# battery_monitor_6803-2_-no_uno.net
KiCad netlist of a schematic drawn in EAGLE
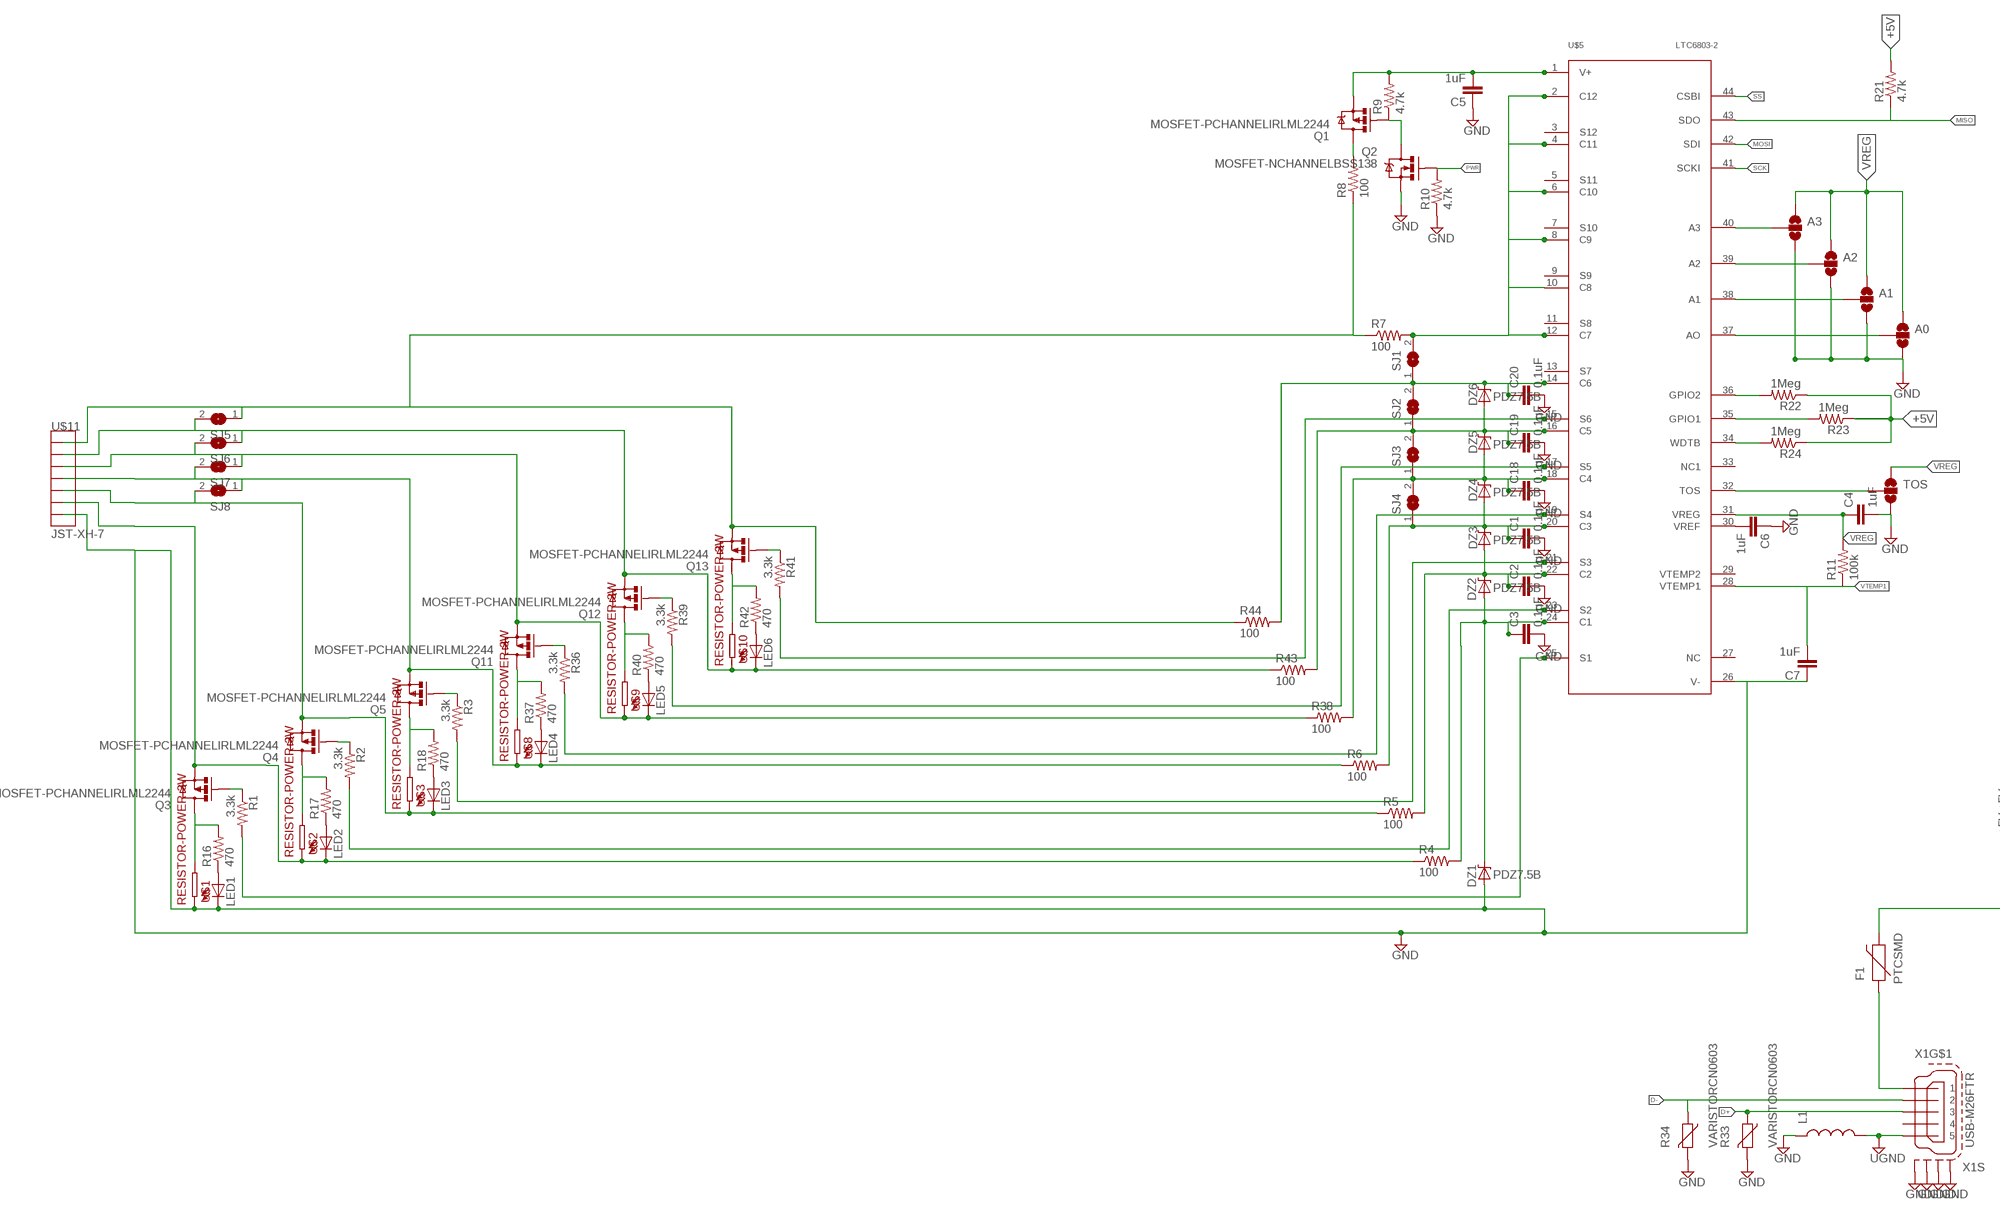
[diagram p0: schematic, sheet 1, part 1 of 2]
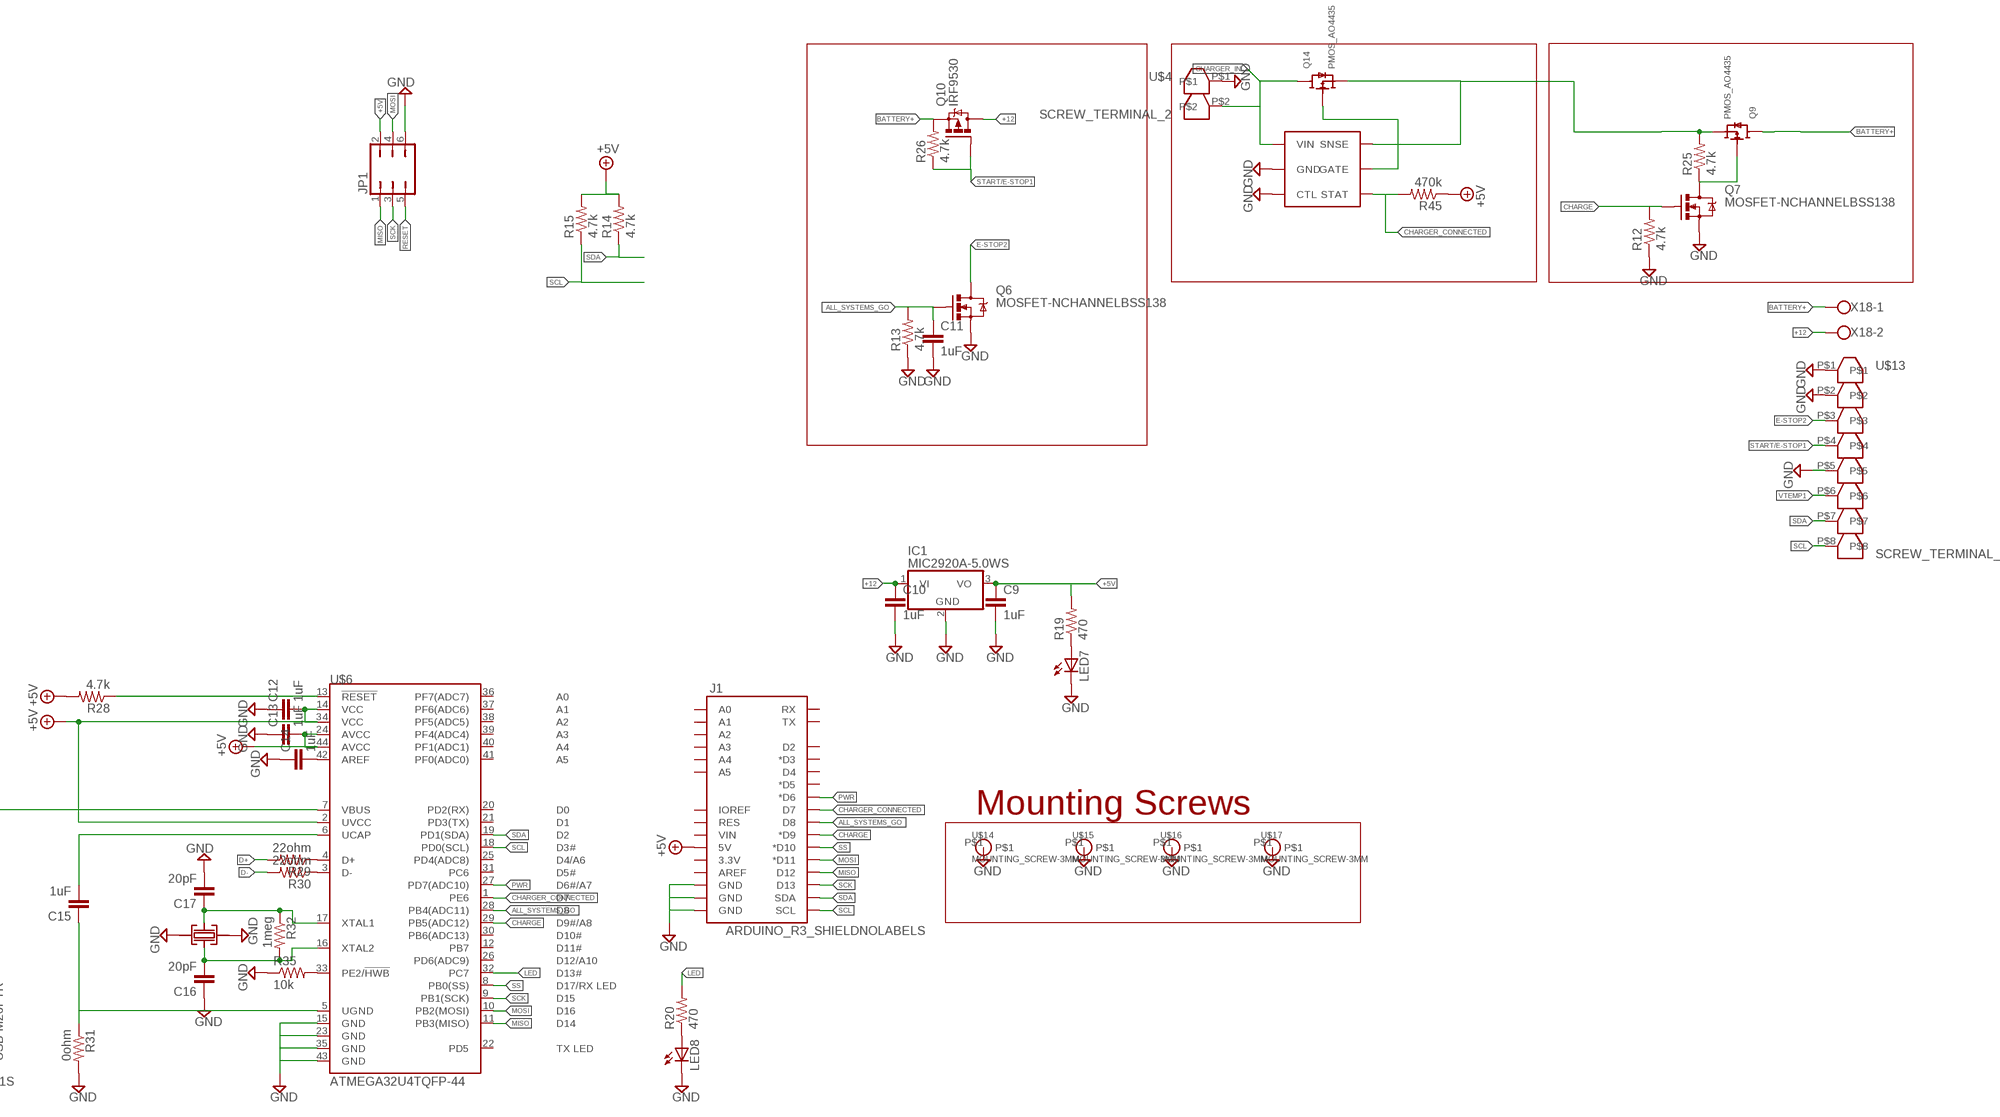
[diagram p1: schematic, sheet 1, part 2 of 2]

(export (version "E")
  (design (tool "Eeschema 10.0.6"))
  (components
    (comp (ref "A0")
      (value "SOLDERJUMPER_2WAYS")
      (footprint "eagle-import:SJ_3")
      (libsource (lib "eagle-import") (part "SOLDERJUMPER_2WAYS"))
    )
    (comp (ref "A1")
      (value "SOLDERJUMPER_2WAYS")
      (footprint "eagle-import:SJ_3")
      (libsource (lib "eagle-import") (part "SOLDERJUMPER_2WAYS"))
    )
    (comp (ref "A2")
      (value "SOLDERJUMPER_2WAYS")
      (footprint "eagle-import:SJ_3")
      (libsource (lib "eagle-import") (part "SOLDERJUMPER_2WAYS"))
    )
    (comp (ref "A3")
      (value "SOLDERJUMPER_2WAYS")
      (footprint "eagle-import:SJ_3")
      (libsource (lib "eagle-import") (part "SOLDERJUMPER_2WAYS"))
    )
    (comp (ref "C1")
      (value "0.1uF")
      (footprint "eagle-import:0603-CAP")
      (fields (field (name "MPN") "0402ZD104KAT2A"))
      (libsource (lib "eagle-import") (part "0.1UF-100V-10%(0603)"))
    )
    (comp (ref "C2")
      (value "0.1uF")
      (footprint "eagle-import:0603-CAP")
      (fields (field (name "MPN") "0402ZD104KAT2A"))
      (libsource (lib "eagle-import") (part "0.1UF-100V-10%(0603)"))
    )
    (comp (ref "C3")
      (value "0.1uF")
      (footprint "eagle-import:0603-CAP")
      (fields (field (name "MPN") "0402ZD104KAT2A"))
      (libsource (lib "eagle-import") (part "0.1UF-100V-10%(0603)"))
    )
    (comp (ref "C4")
      (value "1uF")
      (footprint "eagle-import:0603-CAP")
      (fields (field (name "PROD_ID") "CAP-08390"))
      (libsource (lib "eagle-import") (part "0.1UF-100V-10%(0603)"))
    )
    (comp (ref "C5")
      (value "1uF")
      (footprint "eagle-import:0603-CAP")
      (fields (field (name "PROD_ID") "CAP-08390"))
      (libsource (lib "eagle-import") (part "0.1UF-100V-10%(0603)"))
    )
    (comp (ref "C6")
      (value "1uF")
      (footprint "eagle-import:0603-CAP")
      (fields (field (name "PROD_ID") "CAP-08390"))
      (libsource (lib "eagle-import") (part "0.1UF-100V-10%(0603)"))
    )
    (comp (ref "C7")
      (value "1uF")
      (footprint "eagle-import:0603-CAP")
      (fields (field (name "PROD_ID") "CAP-08390"))
      (libsource (lib "eagle-import") (part "0.1UF-100V-10%(0603)"))
    )
    (comp (ref "C9")
      (value "1uF")
      (footprint "eagle-import:0603-CAP")
      (fields (field (name "PROD_ID") "CAP-08390"))
      (libsource (lib "eagle-import") (part "0.1UF-100V-10%(0603)"))
    )
    (comp (ref "C10")
      (value "1uF")
      (footprint "eagle-import:0603-CAP")
      (fields (field (name "PROD_ID") "CAP-08390"))
      (libsource (lib "eagle-import") (part "0.1UF-100V-10%(0603)"))
    )
    (comp (ref "C11")
      (value "1uF")
      (footprint "eagle-import:0603-CAP")
      (fields (field (name "PROD_ID") "CAP-08390"))
      (libsource (lib "eagle-import") (part "0.1UF-100V-10%(0603)"))
    )
    (comp (ref "C12")
      (value "1uF")
      (footprint "eagle-import:0603-CAP")
      (fields (field (name "PROD_ID") "CAP-08390"))
      (libsource (lib "eagle-import") (part "0.1UF-100V-10%(0603)"))
    )
    (comp (ref "C13")
      (value "1uF")
      (footprint "eagle-import:0603-CAP")
      (fields (field (name "PROD_ID") "CAP-08390"))
      (libsource (lib "eagle-import") (part "0.1UF-100V-10%(0603)"))
    )
    (comp (ref "C14")
      (value "1uF")
      (footprint "eagle-import:0603-CAP")
      (fields (field (name "PROD_ID") "CAP-08390"))
      (libsource (lib "eagle-import") (part "0.1UF-100V-10%(0603)"))
    )
    (comp (ref "C15")
      (value "1uF")
      (footprint "eagle-import:0603-CAP")
      (fields (field (name "PROD_ID") "CAP-08390"))
      (libsource (lib "eagle-import") (part "0.1UF-100V-10%(0603)"))
    )
    (comp (ref "C16")
      (value "20pF")
      (footprint "eagle-import:0603-CAP")
      (fields (field (name "PROD_ID") "CAP-08390"))
      (libsource (lib "eagle-import") (part "0.1UF-100V-10%(0603)"))
    )
    (comp (ref "C17")
      (value "20pF")
      (footprint "eagle-import:0603-CAP")
      (fields (field (name "PROD_ID") "CAP-08390"))
      (libsource (lib "eagle-import") (part "0.1UF-100V-10%(0603)"))
    )
    (comp (ref "C18")
      (value "0.1uF")
      (footprint "eagle-import:0603-CAP")
      (fields (field (name "MPN") "0402ZD104KAT2A") (field (name "PROD_ID") "CAP-08390"))
      (libsource (lib "eagle-import") (part "0.1UF-100V-10%(0603)"))
    )
    (comp (ref "C19")
      (value "0.1uF")
      (footprint "eagle-import:0603-CAP")
      (fields (field (name "MPN") "0402ZD104KAT2A") (field (name "PROD_ID") "CAP-08390"))
      (libsource (lib "eagle-import") (part "0.1UF-100V-10%(0603)"))
    )
    (comp (ref "C20")
      (value "0.1uF")
      (footprint "eagle-import:0603-CAP")
      (fields (field (name "MPN") "0402ZD104KAT2A") (field (name "PROD_ID") "CAP-08390"))
      (libsource (lib "eagle-import") (part "0.1UF-100V-10%(0603)"))
    )
    (comp (ref "DZ1")
      (value "PDZ7.5B")
      (footprint "eagle-import:SOD-323")
      (libsource (lib "eagle-import") (part "DIODE-ZENER-BZT52"))
    )
    (comp (ref "DZ2")
      (value "PDZ7.5B")
      (footprint "eagle-import:SOD-323")
      (libsource (lib "eagle-import") (part "DIODE-ZENER-BZT52"))
    )
    (comp (ref "DZ3")
      (value "PDZ7.5B")
      (footprint "eagle-import:SOD-323")
      (libsource (lib "eagle-import") (part "DIODE-ZENER-BZT52"))
    )
    (comp (ref "DZ4")
      (value "PDZ7.5B")
      (footprint "eagle-import:SOD-323")
      (libsource (lib "eagle-import") (part "DIODE-ZENER-BZT52"))
    )
    (comp (ref "DZ5")
      (value "PDZ7.5B")
      (footprint "eagle-import:SOD-323")
      (libsource (lib "eagle-import") (part "DIODE-ZENER-BZT52"))
    )
    (comp (ref "DZ6")
      (value "PDZ7.5B")
      (footprint "eagle-import:SOD-323")
      (libsource (lib "eagle-import") (part "DIODE-ZENER-BZT52"))
    )
    (comp (ref "F1")
      (value "PTCSMD")
      (footprint "eagle-import:PTC-1206")
      (libsource (lib "eagle-import") (part "PTCSMD"))
    )
    (comp (ref "IC1")
      (value "MIC2920A-5.0WS")
      (footprint "eagle-import:SOT223")
      (libsource (lib "eagle-import") (part "MCP1703DB"))
    )
    (comp (ref "J1")
      (value "ARDUINO_R3_SHIELDNOLABELS")
      (footprint "eagle-import:UNO_R3_SHIELD_NOLABELS")
      (libsource (lib "eagle-import") (part "ARDUINO_R3_SHIELDNOLABELS"))
    )
    (comp (ref "JP1")
      (value "JP3Q")
      (footprint "eagle-import:JP3Q")
      (libsource (lib "eagle-import") (part "JP3Q"))
    )
    (comp (ref "L1")
      (value "INDUCTOR0805")
      (footprint "eagle-import:0805")
      (libsource (lib "eagle-import") (part "INDUCTOR0805"))
    )
    (comp (ref "LED1")
      (value "LED0603")
      (footprint "eagle-import:LED-0603")
      (libsource (lib "eagle-import") (part "LED0603"))
    )
    (comp (ref "LED2")
      (value "LED0603")
      (footprint "eagle-import:LED-0603")
      (libsource (lib "eagle-import") (part "LED0603"))
    )
    (comp (ref "LED3")
      (value "LED0603")
      (footprint "eagle-import:LED-0603")
      (libsource (lib "eagle-import") (part "LED0603"))
    )
    (comp (ref "LED4")
      (value "LED0603")
      (footprint "eagle-import:LED-0603")
      (libsource (lib "eagle-import") (part "LED0603"))
    )
    (comp (ref "LED5")
      (value "LED0603")
      (footprint "eagle-import:LED-0603")
      (libsource (lib "eagle-import") (part "LED0603"))
    )
    (comp (ref "LED6")
      (value "LED0603")
      (footprint "eagle-import:LED-0603")
      (libsource (lib "eagle-import") (part "LED0603"))
    )
    (comp (ref "LED7")
      (value "LED0603")
      (footprint "eagle-import:LED-0603")
      (libsource (lib "eagle-import") (part "LED0603"))
    )
    (comp (ref "LED8")
      (value "LED0603")
      (footprint "eagle-import:LED-0603")
      (libsource (lib "eagle-import") (part "LED0603"))
    )
    (comp (ref "Q1")
      (value "MOSFET-PCHANNELIRLML2244")
      (footprint "eagle-import:SOT23-3")
      (libsource (lib "eagle-import") (part "MOSFET-PCHANNELIRLML2244"))
    )
    (comp (ref "Q2")
      (value "MOSFET-NCHANNELBSS138")
      (footprint "eagle-import:SOT23")
      (libsource (lib "eagle-import") (part "MOSFET-NCHANNELBSS138"))
    )
    (comp (ref "Q3")
      (value "MOSFET-PCHANNELIRLML2244")
      (footprint "eagle-import:SOT23-3")
      (libsource (lib "eagle-import") (part "MOSFET-PCHANNELIRLML2244"))
    )
    (comp (ref "Q4")
      (value "MOSFET-PCHANNELIRLML2244")
      (footprint "eagle-import:SOT23-3")
      (libsource (lib "eagle-import") (part "MOSFET-PCHANNELIRLML2244"))
    )
    (comp (ref "Q5")
      (value "MOSFET-PCHANNELIRLML2244")
      (footprint "eagle-import:SOT23-3")
      (libsource (lib "eagle-import") (part "MOSFET-PCHANNELIRLML2244"))
    )
    (comp (ref "Q6")
      (value "MOSFET-NCHANNELBSS138")
      (footprint "eagle-import:SOT23")
      (libsource (lib "eagle-import") (part "MOSFET-NCHANNELBSS138"))
    )
    (comp (ref "Q7")
      (value "MOSFET-NCHANNELBSS138")
      (footprint "eagle-import:SOT23")
      (libsource (lib "eagle-import") (part "MOSFET-NCHANNELBSS138"))
    )
    (comp (ref "Q9")
      (value "PMOS_AO4435")
      (footprint "eagle-import:SOIC8")
      (libsource (lib "eagle-import") (part "PMOS_AO4435"))
    )
    (comp (ref "Q10")
      (value "IRF9530")
      (footprint "eagle-import:TO220BV")
      (libsource (lib "eagle-import") (part "IRF9530"))
    )
    (comp (ref "Q11")
      (value "MOSFET-PCHANNELIRLML2244")
      (footprint "eagle-import:SOT23-3")
      (libsource (lib "eagle-import") (part "MOSFET-PCHANNELIRLML2244"))
    )
    (comp (ref "Q12")
      (value "MOSFET-PCHANNELIRLML2244")
      (footprint "eagle-import:SOT23-3")
      (libsource (lib "eagle-import") (part "MOSFET-PCHANNELIRLML2244"))
    )
    (comp (ref "Q13")
      (value "MOSFET-PCHANNELIRLML2244")
      (footprint "eagle-import:SOT23-3")
      (libsource (lib "eagle-import") (part "MOSFET-PCHANNELIRLML2244"))
    )
    (comp (ref "Q14")
      (value "PMOS_AO4435")
      (footprint "eagle-import:SOIC8")
      (libsource (lib "eagle-import") (part "PMOS_AO4435"))
    )
    (comp (ref "R1")
      (value "3.3k")
      (footprint "eagle-import:0603-RES")
      (libsource (lib "eagle-import") (part "3.3KOHM1/10W1%(0603)"))
    )
    (comp (ref "R2")
      (value "3.3k")
      (footprint "eagle-import:0603-RES")
      (libsource (lib "eagle-import") (part "3.3KOHM1/10W1%(0603)"))
    )
    (comp (ref "R3")
      (value "3.3k")
      (footprint "eagle-import:0603-RES")
      (libsource (lib "eagle-import") (part "3.3KOHM1/10W1%(0603)"))
    )
    (comp (ref "R4")
      (value "100")
      (footprint "eagle-import:0603-RES")
      (libsource (lib "eagle-import") (part "3.3KOHM1/10W1%(0603)"))
    )
    (comp (ref "R5")
      (value "100")
      (footprint "eagle-import:0603-RES")
      (libsource (lib "eagle-import") (part "3.3KOHM1/10W1%(0603)"))
    )
    (comp (ref "R6")
      (value "100")
      (footprint "eagle-import:0603-RES")
      (libsource (lib "eagle-import") (part "3.3KOHM1/10W1%(0603)"))
    )
    (comp (ref "R7")
      (value "100")
      (footprint "eagle-import:0603-RES")
      (libsource (lib "eagle-import") (part "3.3KOHM1/10W1%(0603)"))
    )
    (comp (ref "R8")
      (value "100")
      (footprint "eagle-import:0603-RES")
      (libsource (lib "eagle-import") (part "3.3KOHM1/10W1%(0603)"))
    )
    (comp (ref "R9")
      (value "4.7k")
      (footprint "eagle-import:0603-RES")
      (libsource (lib "eagle-import") (part "3.3KOHM1/10W1%(0603)"))
    )
    (comp (ref "R10")
      (value "4.7k")
      (footprint "eagle-import:0603-RES")
      (libsource (lib "eagle-import") (part "3.3KOHM1/10W1%(0603)"))
    )
    (comp (ref "R11")
      (value "100k")
      (footprint "eagle-import:0603-RES")
      (libsource (lib "eagle-import") (part "3.3KOHM1/10W1%(0603)"))
    )
    (comp (ref "R12")
      (value "4.7k")
      (footprint "eagle-import:0603-RES")
      (libsource (lib "eagle-import") (part "3.3KOHM1/10W1%(0603)"))
    )
    (comp (ref "R13")
      (value "4.7k")
      (footprint "eagle-import:0603-RES")
      (libsource (lib "eagle-import") (part "3.3KOHM1/10W1%(0603)"))
    )
    (comp (ref "R14")
      (value "4.7k")
      (footprint "eagle-import:0603-RES")
      (libsource (lib "eagle-import") (part "3.3KOHM1/10W1%(0603)"))
    )
    (comp (ref "R15")
      (value "4.7k")
      (footprint "eagle-import:0603-RES")
      (libsource (lib "eagle-import") (part "3.3KOHM1/10W1%(0603)"))
    )
    (comp (ref "R16")
      (value "470")
      (footprint "eagle-import:0603-RES")
      (fields (field (name "PROD_ID") "RES-07851"))
      (libsource (lib "eagle-import") (part "3.3KOHM1/10W1%(0603)"))
    )
    (comp (ref "R17")
      (value "470")
      (footprint "eagle-import:0603-RES")
      (fields (field (name "PROD_ID") "RES-07851"))
      (libsource (lib "eagle-import") (part "3.3KOHM1/10W1%(0603)"))
    )
    (comp (ref "R18")
      (value "470")
      (footprint "eagle-import:0603-RES")
      (fields (field (name "PROD_ID") "RES-07851"))
      (libsource (lib "eagle-import") (part "3.3KOHM1/10W1%(0603)"))
    )
    (comp (ref "R19")
      (value "470")
      (footprint "eagle-import:0603-RES")
      (fields (field (name "PROD_ID") "RES-07851"))
      (libsource (lib "eagle-import") (part "3.3KOHM1/10W1%(0603)"))
    )
    (comp (ref "R20")
      (value "470")
      (footprint "eagle-import:0603-RES")
      (fields (field (name "PROD_ID") "RES-07851"))
      (libsource (lib "eagle-import") (part "3.3KOHM1/10W1%(0603)"))
    )
    (comp (ref "R21")
      (value "4.7k")
      (footprint "eagle-import:0603-RES")
      (fields (field (name "PROD_ID") "RES-07851"))
      (libsource (lib "eagle-import") (part "3.3KOHM1/10W1%(0603)"))
    )
    (comp (ref "R22")
      (value "1Meg")
      (footprint "eagle-import:0603-RES")
      (fields (field (name "PROD_ID") "RES-07851"))
      (libsource (lib "eagle-import") (part "3.3KOHM1/10W1%(0603)"))
    )
    (comp (ref "R23")
      (value "1Meg")
      (footprint "eagle-import:0603-RES")
      (fields (field (name "PROD_ID") "RES-07851"))
      (libsource (lib "eagle-import") (part "3.3KOHM1/10W1%(0603)"))
    )
    (comp (ref "R24")
      (value "1Meg")
      (footprint "eagle-import:0603-RES")
      (fields (field (name "PROD_ID") "RES-07851"))
      (libsource (lib "eagle-import") (part "3.3KOHM1/10W1%(0603)"))
    )
    (comp (ref "R25")
      (value "4.7k")
      (footprint "eagle-import:0603-RES")
      (fields (field (name "PROD_ID") "RES-07851"))
      (libsource (lib "eagle-import") (part "3.3KOHM1/10W1%(0603)"))
    )
    (comp (ref "R26")
      (value "4.7k")
      (footprint "eagle-import:0603-RES")
      (fields (field (name "PROD_ID") "RES-07851"))
      (libsource (lib "eagle-import") (part "3.3KOHM1/10W1%(0603)"))
    )
    (comp (ref "R28")
      (value "4.7k")
      (footprint "eagle-import:0603-RES")
      (fields (field (name "PROD_ID") "RES-07851"))
      (libsource (lib "eagle-import") (part "3.3KOHM1/10W1%(0603)"))
    )
    (comp (ref "R29")
      (value "22ohm")
      (footprint "eagle-import:0603-RES")
      (fields (field (name "PROD_ID") "RES-07851"))
      (libsource (lib "eagle-import") (part "3.3KOHM1/10W1%(0603)"))
    )
    (comp (ref "R30")
      (value "22ohm")
      (footprint "eagle-import:0603-RES")
      (fields (field (name "PROD_ID") "RES-07851"))
      (libsource (lib "eagle-import") (part "3.3KOHM1/10W1%(0603)"))
    )
    (comp (ref "R31")
      (value "0ohm")
      (footprint "eagle-import:0603-RES")
      (fields (field (name "PROD_ID") "RES-07851"))
      (libsource (lib "eagle-import") (part "3.3KOHM1/10W1%(0603)"))
    )
    (comp (ref "R32")
      (value "1meg")
      (footprint "eagle-import:0603-RES")
      (fields (field (name "PROD_ID") "RES-07851"))
      (libsource (lib "eagle-import") (part "3.3KOHM1/10W1%(0603)"))
    )
    (comp (ref "R33")
      (value "VARISTORCN0603")
      (footprint "eagle-import:CT_CN0603")
      (libsource (lib "eagle-import") (part "VARISTORCN0603"))
    )
    (comp (ref "R34")
      (value "VARISTORCN0603")
      (footprint "eagle-import:CT_CN0603")
      (libsource (lib "eagle-import") (part "VARISTORCN0603"))
    )
    (comp (ref "R35")
      (value "10k")
      (footprint "eagle-import:0603-RES")
      (fields (field (name "PROD_ID") "RES-07851"))
      (libsource (lib "eagle-import") (part "3.3KOHM1/10W1%(0603)"))
    )
    (comp (ref "R36")
      (value "3.3k")
      (footprint "eagle-import:0603-RES")
      (libsource (lib "eagle-import") (part "3.3KOHM1/10W1%(0603)"))
    )
    (comp (ref "R37")
      (value "470")
      (footprint "eagle-import:0603-RES")
      (fields (field (name "PROD_ID") "RES-07851"))
      (libsource (lib "eagle-import") (part "3.3KOHM1/10W1%(0603)"))
    )
    (comp (ref "R38")
      (value "100")
      (footprint "eagle-import:0603-RES")
      (fields (field (name "PROD_ID") "RES-07851"))
      (libsource (lib "eagle-import") (part "3.3KOHM1/10W1%(0603)"))
    )
    (comp (ref "R39")
      (value "3.3k")
      (footprint "eagle-import:0603-RES")
      (libsource (lib "eagle-import") (part "3.3KOHM1/10W1%(0603)"))
    )
    (comp (ref "R40")
      (value "470")
      (footprint "eagle-import:0603-RES")
      (fields (field (name "PROD_ID") "RES-07851"))
      (libsource (lib "eagle-import") (part "3.3KOHM1/10W1%(0603)"))
    )
    (comp (ref "R41")
      (value "3.3k")
      (footprint "eagle-import:0603-RES")
      (libsource (lib "eagle-import") (part "3.3KOHM1/10W1%(0603)"))
    )
    (comp (ref "R42")
      (value "470")
      (footprint "eagle-import:0603-RES")
      (fields (field (name "PROD_ID") "RES-07851"))
      (libsource (lib "eagle-import") (part "3.3KOHM1/10W1%(0603)"))
    )
    (comp (ref "R43")
      (value "100")
      (footprint "eagle-import:0603-RES")
      (fields (field (name "PROD_ID") "RES-07851"))
      (libsource (lib "eagle-import") (part "3.3KOHM1/10W1%(0603)"))
    )
    (comp (ref "R44")
      (value "100")
      (footprint "eagle-import:0603-RES")
      (fields (field (name "PROD_ID") "RES-07851"))
      (libsource (lib "eagle-import") (part "3.3KOHM1/10W1%(0603)"))
    )
    (comp (ref "R45")
      (value "470k")
      (footprint "eagle-import:0603-RES")
      (fields (field (name "PROD_ID") "RES-07851"))
      (libsource (lib "eagle-import") (part "3.3KOHM1/10W1%(0603)"))
    )
    (comp (ref "SJ1") (value "SJ") (footprint "eagle-import:SJ") (libsource (lib "eagle-import") (part "SJ")))
    (comp (ref "SJ2") (value "SJ") (footprint "eagle-import:SJ") (libsource (lib "eagle-import") (part "SJ")))
    (comp (ref "SJ3") (value "SJ") (footprint "eagle-import:SJ") (libsource (lib "eagle-import") (part "SJ")))
    (comp (ref "SJ4") (value "SJ") (footprint "eagle-import:SJ") (libsource (lib "eagle-import") (part "SJ")))
    (comp (ref "SJ5") (value "SJ") (footprint "eagle-import:SJ") (libsource (lib "eagle-import") (part "SJ")))
    (comp (ref "SJ6") (value "SJ") (footprint "eagle-import:SJ") (libsource (lib "eagle-import") (part "SJ")))
    (comp (ref "SJ7") (value "SJ") (footprint "eagle-import:SJ") (libsource (lib "eagle-import") (part "SJ")))
    (comp (ref "SJ8") (value "SJ") (footprint "eagle-import:SJ") (libsource (lib "eagle-import") (part "SJ")))
    (comp (ref "TOS")
      (value "SOLDERJUMPER_2WAYS")
      (footprint "eagle-import:SJ_3")
      (libsource (lib "eagle-import") (part "SOLDERJUMPER_2WAYS"))
    )
    (comp (ref "U$1")
      (value "RESISTOR-POWER-3W")
      (footprint "eagle-import:RESISTOR-3W")
      (libsource (lib "eagle-import") (part "RESISTOR-POWER-3W"))
    )
    (comp (ref "U$2")
      (value "RESISTOR-POWER-3W")
      (footprint "eagle-import:RESISTOR-3W")
      (libsource (lib "eagle-import") (part "RESISTOR-POWER-3W"))
    )
    (comp (ref "U$3")
      (value "RESISTOR-POWER-3W")
      (footprint "eagle-import:RESISTOR-3W")
      (libsource (lib "eagle-import") (part "RESISTOR-POWER-3W"))
    )
    (comp (ref "U$4")
      (value "SCREW_TERMINAL_2")
      (footprint "eagle-import:SCREW_TERMINAL_2")
      (libsource (lib "eagle-import") (part "SCREW_TERMINAL_2"))
    )
    (comp (ref "U$5")
      (value "LTC6803-2")
      (footprint "eagle-import:FSOP-44")
      (libsource (lib "eagle-import") (part "LTC6803-2"))
    )
    (comp (ref "U$6")
      (value "ATMEGA32U4TQFP-44")
      (footprint "eagle-import:TQFP44")
      (libsource (lib "eagle-import") (part "ATMEGA32U4TQFP-44"))
    )
    (comp (ref "U$7")
      (value "CRYSTAL_403")
      (footprint "eagle-import:CRYSTAL(DFN,LCC)")
      (libsource (lib "eagle-import") (part "CRYSTAL_403"))
    )
    (comp (ref "U$8")
      (value "RESISTOR-POWER-3W")
      (footprint "eagle-import:RESISTOR-3W")
      (libsource (lib "eagle-import") (part "RESISTOR-POWER-3W"))
    )
    (comp (ref "U$9")
      (value "RESISTOR-POWER-3W")
      (footprint "eagle-import:RESISTOR-3W")
      (libsource (lib "eagle-import") (part "RESISTOR-POWER-3W"))
    )
    (comp (ref "U$10")
      (value "RESISTOR-POWER-3W")
      (footprint "eagle-import:RESISTOR-3W")
      (libsource (lib "eagle-import") (part "RESISTOR-POWER-3W"))
    )
    (comp (ref "U$11")
      (value "JST-XH-7")
      (footprint "eagle-import:JST-XH-7")
      (libsource (lib "eagle-import") (part "JST-XH-7"))
    )
    (comp (ref "U$12")
      (value "LTC4412")
      (footprint "eagle-import:SOT-23-6")
      (libsource (lib "eagle-import") (part "LTC4412"))
    )
    (comp (ref "U$13")
      (value "SCREW_TERMINAL_8")
      (footprint "eagle-import:SCREW_TERMINAL_8")
      (libsource (lib "eagle-import") (part "SCREW_TERMINAL_8"))
    )
    (comp (ref "U$14")
      (value "MOUNTING_SCREW-3MM")
      (footprint "eagle-import:MOUNTING_SCREW-3MM")
      (libsource (lib "eagle-import") (part "MOUNTING_SCREW-3MM"))
    )
    (comp (ref "U$15")
      (value "MOUNTING_SCREW-3MM")
      (footprint "eagle-import:MOUNTING_SCREW-3MM")
      (libsource (lib "eagle-import") (part "MOUNTING_SCREW-3MM"))
    )
    (comp (ref "U$16")
      (value "MOUNTING_SCREW-3MM")
      (footprint "eagle-import:MOUNTING_SCREW-3MM")
      (libsource (lib "eagle-import") (part "MOUNTING_SCREW-3MM"))
    )
    (comp (ref "U$17")
      (value "MOUNTING_SCREW-3MM")
      (footprint "eagle-import:MOUNTING_SCREW-3MM")
      (libsource (lib "eagle-import") (part "MOUNTING_SCREW-3MM"))
    )
    (comp (ref "X1")
      (value "USB-M26FTR")
      (footprint "eagle-import:32005-301")
      (libsource (lib "eagle-import") (part "MINI-USB-SCHIELD-32005-301"))
    )
    (comp (ref "X18")
      (value "W237-102")
      (footprint "eagle-import:W237-102")
      (fields (field (name "MPN") "237-102") (field (name "OC_NEWARK") "unknown"))
      (libsource (lib "eagle-import") (part "W237-102"))
    )
  )
  (nets
    (net (code "1") (name "+5V") (class "Default")
      (node (ref "C12") (pin "2") (pinfunction "2_2") (pintype "passive"))
      (node (ref "C13") (pin "2") (pinfunction "2_2") (pintype "passive"))
      (node (ref "C9") (pin "1") (pinfunction "1_1") (pintype "passive"))
      (node (ref "IC1") (pin "3") (pinfunction "VO_3") (pintype "passive"))
      (node (ref "J1") (pin "5V") (pinfunction "5V_5V") (pintype "bidirectional"))
      (node (ref "JP1") (pin "2") (pinfunction "2_2") (pintype "passive"))
      (node (ref "R14") (pin "2") (pinfunction "2_2") (pintype "passive"))
      (node (ref "R15") (pin "2") (pinfunction "2_2") (pintype "passive"))
      (node (ref "R19") (pin "2") (pinfunction "2_2") (pintype "passive"))
      (node (ref "R21") (pin "2") (pinfunction "2_2") (pintype "passive"))
      (node (ref "R22") (pin "1") (pinfunction "1_1") (pintype "passive"))
      (node (ref "R23") (pin "1") (pinfunction "1_1") (pintype "passive"))
      (node (ref "R24") (pin "1") (pinfunction "1_1") (pintype "passive"))
      (node (ref "R28") (pin "2") (pinfunction "2_2") (pintype "passive"))
      (node (ref "R45") (pin "1") (pinfunction "1_1") (pintype "passive"))
      (node (ref "U$6") (pin "14") (pinfunction "VCC_14") (pintype "bidirectional"))
      (node (ref "U$6") (pin "2") (pinfunction "UVCC_2") (pintype "bidirectional"))
      (node (ref "U$6") (pin "24") (pinfunction "AVCC_24") (pintype "bidirectional"))
      (node (ref "U$6") (pin "34") (pinfunction "VCC_34") (pintype "bidirectional"))
      (node (ref "U$6") (pin "44") (pinfunction "AVCC_44") (pintype "bidirectional"))
    )
    (net (code "2") (name "+12") (class "Default")
      (node (ref "C10") (pin "1") (pinfunction "1_1") (pintype "passive"))
      (node (ref "IC1") (pin "1") (pinfunction "VI_1") (pintype "input"))
      (node (ref "Q10") (pin "D") (pinfunction "D_D") (pintype "passive"))
      (node (ref "X18") (pin "2") (pinfunction "KL_2") (pintype "passive"))
    )
    (net (code "3") (name "ALL_SYSTEMS_GO") (class "Default")
      (node (ref "C11") (pin "1") (pinfunction "1_1") (pintype "passive"))
      (node (ref "J1") (pin "D8") (pinfunction "D8_D8") (pintype "bidirectional"))
      (node (ref "Q6") (pin "1") (pinfunction "G_1") (pintype "passive"))
      (node (ref "R13") (pin "2") (pinfunction "2_2") (pintype "passive"))
      (node (ref "U$6") (pin "28") (pinfunction "PB4(ADC11)_28") (pintype "bidirectional"))
    )
    (net (code "4") (name "BATTERY+") (class "Default")
      (node (ref "Q10") (pin "S") (pinfunction "S_S") (pintype "passive"))
      (node (ref "Q9") (pin "5") (pinfunction "DRAIN_5") (pintype "bidirectional"))
      (node (ref "Q9") (pin "6") (pinfunction "DRAIN_6") (pintype "bidirectional"))
      (node (ref "Q9") (pin "7") (pinfunction "DRAIN_7") (pintype "bidirectional"))
      (node (ref "Q9") (pin "8") (pinfunction "DRAIN_8") (pintype "bidirectional"))
      (node (ref "R26") (pin "2") (pinfunction "2_2") (pintype "passive"))
      (node (ref "X18") (pin "1") (pinfunction "KL_1") (pintype "passive"))
    )
    (net (code "5") (name "CHARGE") (class "Default")
      (node (ref "J1") (pin "D9") (pinfunction "*D9_D9") (pintype "bidirectional"))
      (node (ref "Q7") (pin "1") (pinfunction "G_1") (pintype "passive"))
      (node (ref "R12") (pin "2") (pinfunction "2_2") (pintype "passive"))
      (node (ref "U$6") (pin "29") (pinfunction "PB5(ADC12)_29") (pintype "bidirectional"))
    )
    (net (code "6") (name "CHARGER_CONNECTED") (class "Default")
      (node (ref "J1") (pin "D7") (pinfunction "D7_D7") (pintype "bidirectional"))
      (node (ref "R45") (pin "2") (pinfunction "2_2") (pintype "passive"))
      (node (ref "U$12") (pin "P$4") (pinfunction "STAT_P$4") (pintype "bidirectional"))
      (node (ref "U$6") (pin "1") (pinfunction "PE6_1") (pintype "bidirectional"))
    )
    (net (code "7") (name "CHARGER_IN") (class "Default")
      (node (ref "Q14") (pin "5") (pinfunction "DRAIN_5") (pintype "bidirectional"))
      (node (ref "Q14") (pin "6") (pinfunction "DRAIN_6") (pintype "bidirectional"))
      (node (ref "Q14") (pin "7") (pinfunction "DRAIN_7") (pintype "bidirectional"))
      (node (ref "Q14") (pin "8") (pinfunction "DRAIN_8") (pintype "bidirectional"))
      (node (ref "U$12") (pin "P$1") (pinfunction "VIN_P$1") (pintype "bidirectional"))
      (node (ref "U$4") (pin "P$2") (pinfunction "P$2_P$2") (pintype "bidirectional"))
    )
    (net (code "8") (name "D+") (class "Default")
      (node (ref "R29") (pin "2") (pinfunction "2_2") (pintype "passive"))
      (node (ref "R33") (pin "1") (pinfunction "1_1") (pintype "passive"))
      (node (ref "X1") (pin "3") (pinfunction "3_3") (pintype "passive"))
    )
    (net (code "9") (name "D-") (class "Default")
      (node (ref "R30") (pin "2") (pinfunction "2_2") (pintype "passive"))
      (node (ref "R34") (pin "1") (pinfunction "1_1") (pintype "passive"))
      (node (ref "X1") (pin "2") (pinfunction "2_2") (pintype "passive"))
    )
    (net (code "10") (name "E-STOP2") (class "Default")
      (node (ref "Q6") (pin "3") (pinfunction "D_3") (pintype "passive"))
      (node (ref "U$13") (pin "P$3") (pinfunction "P$3_P$3") (pintype "bidirectional"))
    )
    (net (code "11") (name "GND") (class "Default")
      (node (ref "A0") (pin "3") (pinfunction "3_3") (pintype "passive"))
      (node (ref "A1") (pin "3") (pinfunction "3_3") (pintype "passive"))
      (node (ref "A2") (pin "3") (pinfunction "3_3") (pintype "passive"))
      (node (ref "A3") (pin "3") (pinfunction "3_3") (pintype "passive"))
      (node (ref "C1") (pin "2") (pinfunction "2_2") (pintype "passive"))
      (node (ref "C10") (pin "2") (pinfunction "2_2") (pintype "passive"))
      (node (ref "C11") (pin "2") (pinfunction "2_2") (pintype "passive"))
      (node (ref "C12") (pin "1") (pinfunction "1_1") (pintype "passive"))
      (node (ref "C13") (pin "1") (pinfunction "1_1") (pintype "passive"))
      (node (ref "C14") (pin "1") (pinfunction "1_1") (pintype "passive"))
      (node (ref "C16") (pin "1") (pinfunction "1_1") (pintype "passive"))
      (node (ref "C17") (pin "2") (pinfunction "2_2") (pintype "passive"))
      (node (ref "C18") (pin "2") (pinfunction "2_2") (pintype "passive"))
      (node (ref "C19") (pin "2") (pinfunction "2_2") (pintype "passive"))
      (node (ref "C2") (pin "2") (pinfunction "2_2") (pintype "passive"))
      (node (ref "C20") (pin "2") (pinfunction "2_2") (pintype "passive"))
      (node (ref "C3") (pin "2") (pinfunction "2_2") (pintype "passive"))
      (node (ref "C4") (pin "2") (pinfunction "2_2") (pintype "passive"))
      (node (ref "C5") (pin "1") (pinfunction "1_1") (pintype "passive"))
      (node (ref "C6") (pin "1") (pinfunction "1_1") (pintype "passive"))
      (node (ref "C7") (pin "1") (pinfunction "1_1") (pintype "passive"))
      (node (ref "C9") (pin "2") (pinfunction "2_2") (pintype "passive"))
      (node (ref "DZ1") (pin "2") (pinfunction "A_2") (pintype "passive"))
      (node (ref "IC1") (pin "2") (pinfunction "GND_2") (pintype "passive"))
      (node (ref "J1") (pin "GND@0") (pinfunction "GND_GND@0") (pintype "bidirectional"))
      (node (ref "J1") (pin "GND@1") (pinfunction "GND_GND@1") (pintype "bidirectional"))
      (node (ref "J1") (pin "GND@2") (pinfunction "GND_GND@2") (pintype "bidirectional"))
      (node (ref "JP1") (pin "6") (pinfunction "6_6") (pintype "passive"))
      (node (ref "L1") (pin "1") (pinfunction "1_1") (pintype "passive"))
      (node (ref "LED1") (pin "C") (pinfunction "C_C") (pintype "passive"))
      (node (ref "LED7") (pin "C") (pinfunction "C_C") (pintype "passive"))
      (node (ref "LED8") (pin "C") (pinfunction "C_C") (pintype "passive"))
      (node (ref "Q2") (pin "2") (pinfunction "S_2") (pintype "passive"))
      (node (ref "Q6") (pin "2") (pinfunction "S_2") (pintype "passive"))
      (node (ref "Q7") (pin "2") (pinfunction "S_2") (pintype "passive"))
      (node (ref "R10") (pin "1") (pinfunction "1_1") (pintype "passive"))
      (node (ref "R12") (pin "1") (pinfunction "1_1") (pintype "passive"))
      (node (ref "R13") (pin "1") (pinfunction "1_1") (pintype "passive"))
      (node (ref "R31") (pin "2") (pinfunction "2_2") (pintype "passive"))
      (node (ref "R33") (pin "2") (pinfunction "2_2") (pintype "passive"))
      (node (ref "R34") (pin "2") (pinfunction "2_2") (pintype "passive"))
      (node (ref "R35") (pin "1") (pinfunction "1_1") (pintype "passive"))
      (node (ref "TOS") (pin "3") (pinfunction "3_3") (pintype "passive"))
      (node (ref "U$1") (pin "P$2") (pinfunction "P$2_P$2") (pintype "bidirectional"))
      (node (ref "U$11") (pin "1") (pinfunction "1_1") (pintype "bidirectional"))
      (node (ref "U$12") (pin "P$2") (pinfunction "GND_P$2") (pintype "bidirectional"))
      (node (ref "U$12") (pin "P$3") (pinfunction "CTL_P$3") (pintype "bidirectional"))
      (node (ref "U$13") (pin "P$1") (pinfunction "P$1_P$1") (pintype "bidirectional"))
      (node (ref "U$13") (pin "P$2") (pinfunction "P$2_P$2") (pintype "bidirectional"))
      (node (ref "U$13") (pin "P$5") (pinfunction "P$5_P$5") (pintype "bidirectional"))
      (node (ref "U$14") (pin "P$1") (pinfunction "P$1_P$1") (pintype "bidirectional"))
      (node (ref "U$15") (pin "P$1") (pinfunction "P$1_P$1") (pintype "bidirectional"))
      (node (ref "U$16") (pin "P$1") (pinfunction "P$1_P$1") (pintype "bidirectional"))
      (node (ref "U$17") (pin "P$1") (pinfunction "P$1_P$1") (pintype "bidirectional"))
      (node (ref "U$4") (pin "P$1") (pinfunction "P$1_P$1") (pintype "bidirectional"))
      (node (ref "U$5") (pin "26") (pinfunction "V-_26") (pintype "bidirectional"))
      (node (ref "U$6") (pin "15") (pinfunction "GND_15") (pintype "bidirectional"))
      (node (ref "U$6") (pin "23") (pinfunction "GND_23") (pintype "bidirectional"))
      (node (ref "U$6") (pin "35") (pinfunction "GND_35") (pintype "bidirectional"))
      (node (ref "U$6") (pin "43") (pinfunction "GND_43") (pintype "bidirectional"))
      (node (ref "U$7") (pin "CASE") (pinfunction "CASE_CASE") (pintype "bidirectional"))
      (node (ref "U$7") (pin "CASE1") (pinfunction "CASE1_CASE1") (pintype "bidirectional"))
      (node (ref "X1") (pin "M1") (pinfunction "S1_M1") (pintype "passive"))
      (node (ref "X1") (pin "M2") (pinfunction "S2_M2") (pintype "passive"))
      (node (ref "X1") (pin "M3") (pinfunction "S3_M3") (pintype "passive"))
      (node (ref "X1") (pin "M4") (pinfunction "S4_M4") (pintype "passive"))
    )
    (net (code "12") (name "LED") (class "Default")
      (node (ref "R20") (pin "2") (pinfunction "2_2") (pintype "passive"))
      (node (ref "U$6") (pin "32") (pinfunction "PC7_32") (pintype "bidirectional"))
    )
    (net (code "13") (name "MISO") (class "Default")
      (node (ref "J1") (pin "D12") (pinfunction "D12_D12") (pintype "bidirectional"))
      (node (ref "JP1") (pin "1") (pinfunction "1_1") (pintype "passive"))
      (node (ref "R21") (pin "1") (pinfunction "1_1") (pintype "passive"))
      (node (ref "U$5") (pin "43") (pinfunction "SDO_43") (pintype "bidirectional"))
      (node (ref "U$6") (pin "11") (pinfunction "PB3(MISO)_11") (pintype "bidirectional"))
    )
    (net (code "14") (name "MOSI") (class "Default")
      (node (ref "J1") (pin "D11") (pinfunction "*D11_D11") (pintype "bidirectional"))
      (node (ref "JP1") (pin "4") (pinfunction "4_4") (pintype "passive"))
      (node (ref "U$5") (pin "42") (pinfunction "SDI_42") (pintype "bidirectional"))
      (node (ref "U$6") (pin "10") (pinfunction "PB2(MOSI)_10") (pintype "bidirectional"))
    )
    (net (code "15") (name "Net-(DZ1-C)") (class "Default")
      (node (ref "C3") (pin "1") (pinfunction "1_1") (pintype "passive"))
      (node (ref "DZ1") (pin "1") (pinfunction "C_1") (pintype "passive"))
      (node (ref "DZ2") (pin "2") (pinfunction "A_2") (pintype "passive"))
      (node (ref "R4") (pin "2") (pinfunction "2_2") (pintype "passive"))
      (node (ref "U$5") (pin "24") (pinfunction "C1_24") (pintype "bidirectional"))
    )
    (net (code "16") (name "Net-(DZ2-C)") (class "Default")
      (node (ref "C2") (pin "1") (pinfunction "1_1") (pintype "passive"))
      (node (ref "DZ2") (pin "1") (pinfunction "C_1") (pintype "passive"))
      (node (ref "DZ3") (pin "2") (pinfunction "A_2") (pintype "passive"))
      (node (ref "R5") (pin "2") (pinfunction "2_2") (pintype "passive"))
      (node (ref "U$5") (pin "22") (pinfunction "C2_22") (pintype "bidirectional"))
    )
    (net (code "17") (name "Net-(DZ3-C)") (class "Default")
      (node (ref "C1") (pin "1") (pinfunction "1_1") (pintype "passive"))
      (node (ref "DZ3") (pin "1") (pinfunction "C_1") (pintype "passive"))
      (node (ref "DZ4") (pin "2") (pinfunction "A_2") (pintype "passive"))
      (node (ref "R6") (pin "2") (pinfunction "2_2") (pintype "passive"))
      (node (ref "SJ4") (pin "1") (pinfunction "1_1") (pintype "passive"))
      (node (ref "U$5") (pin "20") (pinfunction "C3_20") (pintype "bidirectional"))
    )
    (net (code "18") (name "Net-(DZ4-C)") (class "Default")
      (node (ref "C18") (pin "1") (pinfunction "1_1") (pintype "passive"))
      (node (ref "DZ4") (pin "1") (pinfunction "C_1") (pintype "passive"))
      (node (ref "DZ5") (pin "2") (pinfunction "A_2") (pintype "passive"))
      (node (ref "R38") (pin "2") (pinfunction "2_2") (pintype "passive"))
      (node (ref "SJ3") (pin "1") (pinfunction "1_1") (pintype "passive"))
      (node (ref "SJ4") (pin "2") (pinfunction "2_2") (pintype "passive"))
      (node (ref "U$5") (pin "18") (pinfunction "C4_18") (pintype "bidirectional"))
    )
    (net (code "19") (name "Net-(DZ5-C)") (class "Default")
      (node (ref "C19") (pin "1") (pinfunction "1_1") (pintype "passive"))
      (node (ref "DZ5") (pin "1") (pinfunction "C_1") (pintype "passive"))
      (node (ref "DZ6") (pin "2") (pinfunction "A_2") (pintype "passive"))
      (node (ref "R43") (pin "2") (pinfunction "2_2") (pintype "passive"))
      (node (ref "SJ2") (pin "1") (pinfunction "1_1") (pintype "passive"))
      (node (ref "SJ3") (pin "2") (pinfunction "2_2") (pintype "passive"))
      (node (ref "U$5") (pin "16") (pinfunction "C5_16") (pintype "bidirectional"))
    )
    (net (code "20") (name "Net-(DZ6-C)") (class "Default")
      (node (ref "C20") (pin "1") (pinfunction "1_1") (pintype "passive"))
      (node (ref "DZ6") (pin "1") (pinfunction "C_1") (pintype "passive"))
      (node (ref "R44") (pin "2") (pinfunction "2_2") (pintype "passive"))
      (node (ref "SJ1") (pin "1") (pinfunction "1_1") (pintype "passive"))
      (node (ref "SJ2") (pin "2") (pinfunction "2_2") (pintype "passive"))
      (node (ref "U$5") (pin "14") (pinfunction "C6_14") (pintype "bidirectional"))
    )
    (net (code "21") (name "Net-(F1-Pad1)") (class "Default")
      (node (ref "F1") (pin "1") (pinfunction "1_1") (pintype "bidirectional"))
      (node (ref "X1") (pin "1") (pinfunction "1_1") (pintype "passive"))
    )
    (net (code "22") (name "Net-(LED1-PadA)") (class "Default")
      (node (ref "LED1") (pin "A") (pinfunction "A_A") (pintype "passive"))
      (node (ref "R16") (pin "1") (pinfunction "1_1") (pintype "passive"))
    )
    (net (code "23") (name "Net-(LED2-PadA)") (class "Default")
      (node (ref "LED2") (pin "A") (pinfunction "A_A") (pintype "passive"))
      (node (ref "R17") (pin "1") (pinfunction "1_1") (pintype "passive"))
    )
    (net (code "24") (name "Net-(LED3-PadA)") (class "Default")
      (node (ref "LED3") (pin "A") (pinfunction "A_A") (pintype "passive"))
      (node (ref "R18") (pin "1") (pinfunction "1_1") (pintype "passive"))
    )
    (net (code "25") (name "Net-(LED4-PadA)") (class "Default")
      (node (ref "LED4") (pin "A") (pinfunction "A_A") (pintype "passive"))
      (node (ref "R37") (pin "1") (pinfunction "1_1") (pintype "passive"))
    )
    (net (code "26") (name "Net-(LED5-PadA)") (class "Default")
      (node (ref "LED5") (pin "A") (pinfunction "A_A") (pintype "passive"))
      (node (ref "R40") (pin "1") (pinfunction "1_1") (pintype "passive"))
    )
    (net (code "27") (name "Net-(LED6-PadA)") (class "Default")
      (node (ref "LED6") (pin "A") (pinfunction "A_A") (pintype "passive"))
      (node (ref "R42") (pin "1") (pinfunction "1_1") (pintype "passive"))
    )
    (net (code "28") (name "Net-(LED7-PadA)") (class "Default")
      (node (ref "LED7") (pin "A") (pinfunction "A_A") (pintype "passive"))
      (node (ref "R19") (pin "1") (pinfunction "1_1") (pintype "passive"))
    )
    (net (code "29") (name "Net-(LED8-PadA)") (class "Default")
      (node (ref "LED8") (pin "A") (pinfunction "A_A") (pintype "passive"))
      (node (ref "R20") (pin "1") (pinfunction "1_1") (pintype "passive"))
    )
    (net (code "30") (name "Net-(Q1-D)") (class "Default")
      (node (ref "Q1") (pin "3") (pinfunction "D_3") (pintype "passive"))
      (node (ref "R8") (pin "2") (pinfunction "2_2") (pintype "passive"))
    )
    (net (code "31") (name "Net-(Q1-G)") (class "Default")
      (node (ref "Q1") (pin "1") (pinfunction "G_1") (pintype "passive"))
      (node (ref "Q2") (pin "3") (pinfunction "D_3") (pintype "passive"))
      (node (ref "R9") (pin "1") (pinfunction "1_1") (pintype "passive"))
    )
    (net (code "32") (name "Net-(Q1-S)") (class "Default")
      (node (ref "C5") (pin "2") (pinfunction "2_2") (pintype "passive"))
      (node (ref "Q1") (pin "2") (pinfunction "S_2") (pintype "passive"))
      (node (ref "R9") (pin "2") (pinfunction "2_2") (pintype "passive"))
      (node (ref "U$5") (pin "1") (pinfunction "V+_1") (pintype "bidirectional"))
    )
    (net (code "33") (name "Net-(Q3-D)") (class "Default")
      (node (ref "Q3") (pin "3") (pinfunction "D_3") (pintype "passive"))
      (node (ref "R16") (pin "2") (pinfunction "2_2") (pintype "passive"))
      (node (ref "U$1") (pin "P$1") (pinfunction "P$1_P$1") (pintype "bidirectional"))
    )
    (net (code "34") (name "Net-(Q3-G)") (class "Default")
      (node (ref "Q3") (pin "1") (pinfunction "G_1") (pintype "passive"))
      (node (ref "R1") (pin "1") (pinfunction "1_1") (pintype "passive"))
    )
    (net (code "35") (name "Net-(Q3-S)") (class "Default")
      (node (ref "LED2") (pin "C") (pinfunction "C_C") (pintype "passive"))
      (node (ref "Q3") (pin "2") (pinfunction "S_2") (pintype "passive"))
      (node (ref "R4") (pin "1") (pinfunction "1_1") (pintype "passive"))
      (node (ref "U$11") (pin "2") (pinfunction "2_2") (pintype "bidirectional"))
      (node (ref "U$2") (pin "P$2") (pinfunction "P$2_P$2") (pintype "bidirectional"))
    )
    (net (code "36") (name "Net-(Q4-D)") (class "Default")
      (node (ref "Q4") (pin "3") (pinfunction "D_3") (pintype "passive"))
      (node (ref "R17") (pin "2") (pinfunction "2_2") (pintype "passive"))
      (node (ref "U$2") (pin "P$1") (pinfunction "P$1_P$1") (pintype "bidirectional"))
    )
    (net (code "37") (name "Net-(Q4-G)") (class "Default")
      (node (ref "Q4") (pin "1") (pinfunction "G_1") (pintype "passive"))
      (node (ref "R2") (pin "1") (pinfunction "1_1") (pintype "passive"))
    )
    (net (code "38") (name "Net-(Q4-S)") (class "Default")
      (node (ref "LED3") (pin "C") (pinfunction "C_C") (pintype "passive"))
      (node (ref "Q4") (pin "2") (pinfunction "S_2") (pintype "passive"))
      (node (ref "R5") (pin "1") (pinfunction "1_1") (pintype "passive"))
      (node (ref "SJ8") (pin "2") (pinfunction "2_2") (pintype "passive"))
      (node (ref "U$11") (pin "3") (pinfunction "3_3") (pintype "bidirectional"))
      (node (ref "U$3") (pin "P$2") (pinfunction "P$2_P$2") (pintype "bidirectional"))
    )
    (net (code "39") (name "Net-(Q5-D)") (class "Default")
      (node (ref "Q5") (pin "3") (pinfunction "D_3") (pintype "passive"))
      (node (ref "R18") (pin "2") (pinfunction "2_2") (pintype "passive"))
      (node (ref "U$3") (pin "P$1") (pinfunction "P$1_P$1") (pintype "bidirectional"))
    )
    (net (code "40") (name "Net-(Q5-G)") (class "Default")
      (node (ref "Q5") (pin "1") (pinfunction "G_1") (pintype "passive"))
      (node (ref "R3") (pin "1") (pinfunction "1_1") (pintype "passive"))
    )
    (net (code "41") (name "Net-(Q5-S)") (class "Default")
      (node (ref "LED4") (pin "C") (pinfunction "C_C") (pintype "passive"))
      (node (ref "Q5") (pin "2") (pinfunction "S_2") (pintype "passive"))
      (node (ref "R6") (pin "1") (pinfunction "1_1") (pintype "passive"))
      (node (ref "SJ7") (pin "2") (pinfunction "2_2") (pintype "passive"))
      (node (ref "SJ8") (pin "1") (pinfunction "1_1") (pintype "passive"))
      (node (ref "U$11") (pin "4") (pinfunction "4_4") (pintype "bidirectional"))
      (node (ref "U$8") (pin "P$2") (pinfunction "P$2_P$2") (pintype "bidirectional"))
    )
    (net (code "42") (name "Net-(Q7-D)") (class "Default")
      (node (ref "Q7") (pin "3") (pinfunction "D_3") (pintype "passive"))
      (node (ref "Q9") (pin "4") (pinfunction "GATE_4") (pintype "bidirectional"))
      (node (ref "R25") (pin "1") (pinfunction "1_1") (pintype "passive"))
    )
    (net (code "43") (name "Net-(Q11-D)") (class "Default")
      (node (ref "Q11") (pin "3") (pinfunction "D_3") (pintype "passive"))
      (node (ref "R37") (pin "2") (pinfunction "2_2") (pintype "passive"))
      (node (ref "U$8") (pin "P$1") (pinfunction "P$1_P$1") (pintype "bidirectional"))
    )
    (net (code "44") (name "Net-(Q11-G)") (class "Default")
      (node (ref "Q11") (pin "1") (pinfunction "G_1") (pintype "passive"))
      (node (ref "R36") (pin "1") (pinfunction "1_1") (pintype "passive"))
    )
    (net (code "45") (name "Net-(Q11-S)") (class "Default")
      (node (ref "LED5") (pin "C") (pinfunction "C_C") (pintype "passive"))
      (node (ref "Q11") (pin "2") (pinfunction "S_2") (pintype "passive"))
      (node (ref "R38") (pin "1") (pinfunction "1_1") (pintype "passive"))
      (node (ref "SJ6") (pin "2") (pinfunction "2_2") (pintype "passive"))
      (node (ref "SJ7") (pin "1") (pinfunction "1_1") (pintype "passive"))
      (node (ref "U$11") (pin "5") (pinfunction "5_5") (pintype "bidirectional"))
      (node (ref "U$9") (pin "P$2") (pinfunction "P$2_P$2") (pintype "bidirectional"))
    )
    (net (code "46") (name "Net-(Q12-D)") (class "Default")
      (node (ref "Q12") (pin "3") (pinfunction "D_3") (pintype "passive"))
      (node (ref "R40") (pin "2") (pinfunction "2_2") (pintype "passive"))
      (node (ref "U$9") (pin "P$1") (pinfunction "P$1_P$1") (pintype "bidirectional"))
    )
    (net (code "47") (name "Net-(Q12-G)") (class "Default")
      (node (ref "Q12") (pin "1") (pinfunction "G_1") (pintype "passive"))
      (node (ref "R39") (pin "1") (pinfunction "1_1") (pintype "passive"))
    )
    (net (code "48") (name "Net-(Q12-S)") (class "Default")
      (node (ref "LED6") (pin "C") (pinfunction "C_C") (pintype "passive"))
      (node (ref "Q12") (pin "2") (pinfunction "S_2") (pintype "passive"))
      (node (ref "R43") (pin "1") (pinfunction "1_1") (pintype "passive"))
      (node (ref "SJ5") (pin "2") (pinfunction "2_2") (pintype "passive"))
      (node (ref "SJ6") (pin "1") (pinfunction "1_1") (pintype "passive"))
      (node (ref "U$10") (pin "P$2") (pinfunction "P$2_P$2") (pintype "bidirectional"))
      (node (ref "U$11") (pin "6") (pinfunction "6_6") (pintype "bidirectional"))
    )
    (net (code "49") (name "Net-(Q13-D)") (class "Default")
      (node (ref "Q13") (pin "3") (pinfunction "D_3") (pintype "passive"))
      (node (ref "R42") (pin "2") (pinfunction "2_2") (pintype "passive"))
      (node (ref "U$10") (pin "P$1") (pinfunction "P$1_P$1") (pintype "bidirectional"))
    )
    (net (code "50") (name "Net-(Q13-G)") (class "Default")
      (node (ref "Q13") (pin "1") (pinfunction "G_1") (pintype "passive"))
      (node (ref "R41") (pin "1") (pinfunction "1_1") (pintype "passive"))
    )
    (net (code "51") (name "Net-(Q13-S)") (class "Default")
      (node (ref "Q13") (pin "2") (pinfunction "S_2") (pintype "passive"))
      (node (ref "R44") (pin "1") (pinfunction "1_1") (pintype "passive"))
      (node (ref "R7") (pin "1") (pinfunction "1_1") (pintype "passive"))
      (node (ref "R8") (pin "1") (pinfunction "1_1") (pintype "passive"))
      (node (ref "SJ5") (pin "1") (pinfunction "1_1") (pintype "passive"))
      (node (ref "U$11") (pin "7") (pinfunction "7_7") (pintype "bidirectional"))
    )
    (net (code "52") (name "Net-(Q14-GATE)") (class "Default")
      (node (ref "Q14") (pin "4") (pinfunction "GATE_4") (pintype "bidirectional"))
      (node (ref "U$12") (pin "P$5") (pinfunction "GATE_P$5") (pintype "bidirectional"))
    )
    (net (code "53") (name "Net-(U$5-A1)") (class "Default")
      (node (ref "A1") (pin "2") (pinfunction "2_2") (pintype "passive"))
      (node (ref "U$5") (pin "38") (pinfunction "A1_38") (pintype "bidirectional"))
    )
    (net (code "54") (name "Net-(U$5-A2)") (class "Default")
      (node (ref "A2") (pin "2") (pinfunction "2_2") (pintype "passive"))
      (node (ref "U$5") (pin "39") (pinfunction "A2_39") (pintype "bidirectional"))
    )
    (net (code "55") (name "Net-(U$5-A3)") (class "Default")
      (node (ref "A3") (pin "2") (pinfunction "2_2") (pintype "passive"))
      (node (ref "U$5") (pin "40") (pinfunction "A3_40") (pintype "bidirectional"))
    )
    (net (code "56") (name "Net-(U$5-AO)") (class "Default")
      (node (ref "A0") (pin "2") (pinfunction "2_2") (pintype "passive"))
      (node (ref "U$5") (pin "37") (pinfunction "AO_37") (pintype "bidirectional"))
    )
    (net (code "57") (name "Net-(U$5-C10)") (class "Default")
      (node (ref "R7") (pin "2") (pinfunction "2_2") (pintype "passive"))
      (node (ref "SJ1") (pin "2") (pinfunction "2_2") (pintype "passive"))
      (node (ref "U$5") (pin "10") (pinfunction "C8_10") (pintype "bidirectional"))
      (node (ref "U$5") (pin "12") (pinfunction "C7_12") (pintype "bidirectional"))
      (node (ref "U$5") (pin "2") (pinfunction "C12_2") (pintype "bidirectional"))
      (node (ref "U$5") (pin "4") (pinfunction "C11_4") (pintype "bidirectional"))
      (node (ref "U$5") (pin "6") (pinfunction "C10_6") (pintype "bidirectional"))
      (node (ref "U$5") (pin "8") (pinfunction "C9_8") (pintype "bidirectional"))
    )
    (net (code "58") (name "Net-(U$5-GPIO1)") (class "Default")
      (node (ref "R23") (pin "2") (pinfunction "2_2") (pintype "passive"))
      (node (ref "U$5") (pin "35") (pinfunction "GPIO1_35") (pintype "bidirectional"))
    )
    (net (code "59") (name "Net-(U$5-GPIO2)") (class "Default")
      (node (ref "R22") (pin "2") (pinfunction "2_2") (pintype "passive"))
      (node (ref "U$5") (pin "36") (pinfunction "GPIO2_36") (pintype "bidirectional"))
    )
    (net (code "60") (name "Net-(U$5-S1)") (class "Default")
      (node (ref "R1") (pin "2") (pinfunction "2_2") (pintype "passive"))
      (node (ref "U$5") (pin "25") (pinfunction "S1_25") (pintype "bidirectional"))
    )
    (net (code "61") (name "Net-(U$5-S2)") (class "Default")
      (node (ref "R2") (pin "2") (pinfunction "2_2") (pintype "passive"))
      (node (ref "U$5") (pin "23") (pinfunction "S2_23") (pintype "bidirectional"))
    )
    (net (code "62") (name "Net-(U$5-S3)") (class "Default")
      (node (ref "R3") (pin "2") (pinfunction "2_2") (pintype "passive"))
      (node (ref "U$5") (pin "21") (pinfunction "S3_21") (pintype "bidirectional"))
    )
    (net (code "63") (name "Net-(U$5-S4)") (class "Default")
      (node (ref "R36") (pin "2") (pinfunction "2_2") (pintype "passive"))
      (node (ref "U$5") (pin "19") (pinfunction "S4_19") (pintype "bidirectional"))
    )
    (net (code "64") (name "Net-(U$5-S5)") (class "Default")
      (node (ref "R39") (pin "2") (pinfunction "2_2") (pintype "passive"))
      (node (ref "U$5") (pin "17") (pinfunction "S5_17") (pintype "bidirectional"))
    )
    (net (code "65") (name "Net-(U$5-S6)") (class "Default")
      (node (ref "R41") (pin "2") (pinfunction "2_2") (pintype "passive"))
      (node (ref "U$5") (pin "15") (pinfunction "S6_15") (pintype "bidirectional"))
    )
    (net (code "66") (name "Net-(U$5-TOS)") (class "Default")
      (node (ref "TOS") (pin "2") (pinfunction "2_2") (pintype "passive"))
      (node (ref "U$5") (pin "32") (pinfunction "TOS_32") (pintype "bidirectional"))
    )
    (net (code "67") (name "Net-(U$5-VREF)") (class "Default")
      (node (ref "C6") (pin "2") (pinfunction "2_2") (pintype "passive"))
      (node (ref "U$5") (pin "30") (pinfunction "VREF_30") (pintype "bidirectional"))
    )
    (net (code "68") (name "Net-(U$5-WDTB)") (class "Default")
      (node (ref "R24") (pin "2") (pinfunction "2_2") (pintype "passive"))
      (node (ref "U$5") (pin "34") (pinfunction "WDTB_34") (pintype "bidirectional"))
    )
    (net (code "69") (name "Net-(U$6-AREF)") (class "Default")
      (node (ref "C14") (pin "2") (pinfunction "2_2") (pintype "passive"))
      (node (ref "U$6") (pin "42") (pinfunction "AREF_42") (pintype "bidirectional"))
    )
    (net (code "70") (name "Net-(U$6-D+)") (class "Default")
      (node (ref "R29") (pin "1") (pinfunction "1_1") (pintype "passive"))
      (node (ref "U$6") (pin "4") (pinfunction "D+_4") (pintype "bidirectional"))
    )
    (net (code "71") (name "Net-(U$6-D-)") (class "Default")
      (node (ref "R30") (pin "1") (pinfunction "1_1") (pintype "passive"))
      (node (ref "U$6") (pin "3") (pinfunction "D-_3") (pintype "bidirectional"))
    )
    (net (code "72") (name "Net-(U$6-PE2{slash}~{HWB})") (class "Default")
      (node (ref "R35") (pin "2") (pinfunction "2_2") (pintype "passive"))
      (node (ref "U$6") (pin "33") (pinfunction "PE2/~{HWB}_33") (pintype "bidirectional"))
    )
    (net (code "73") (name "Net-(U$6-UCAP)") (class "Default")
      (node (ref "C15") (pin "2") (pinfunction "2_2") (pintype "passive"))
      (node (ref "U$6") (pin "6") (pinfunction "UCAP_6") (pintype "bidirectional"))
    )
    (net (code "74") (name "Net-(U$6-VBUS)") (class "Default")
      (node (ref "F1") (pin "2") (pinfunction "2_2") (pintype "bidirectional"))
      (node (ref "U$6") (pin "7") (pinfunction "VBUS_7") (pintype "bidirectional"))
    )
    (net (code "75") (name "Net-(U$6-XTAL1)") (class "Default")
      (node (ref "C17") (pin "1") (pinfunction "1_1") (pintype "passive"))
      (node (ref "R32") (pin "1") (pinfunction "1_1") (pintype "passive"))
      (node (ref "U$6") (pin "17") (pinfunction "XTAL1_17") (pintype "bidirectional"))
      (node (ref "U$7") (pin "IN") (pinfunction "IN_IN") (pintype "bidirectional"))
    )
    (net (code "76") (name "Net-(U$6-XTAL2)") (class "Default")
      (node (ref "C16") (pin "2") (pinfunction "2_2") (pintype "passive"))
      (node (ref "R32") (pin "2") (pinfunction "2_2") (pintype "passive"))
      (node (ref "U$6") (pin "16") (pinfunction "XTAL2_16") (pintype "bidirectional"))
      (node (ref "U$7") (pin "OUT") (pinfunction "OUT_OUT") (pintype "bidirectional"))
    )
    (net (code "77") (name "Net-(U$12-SNSE)") (class "Default")
      (node (ref "Q14") (pin "1") (pinfunction "SOURCE_1") (pintype "bidirectional"))
      (node (ref "Q14") (pin "2") (pinfunction "SOURCE_2") (pintype "bidirectional"))
      (node (ref "Q14") (pin "3") (pinfunction "SOURCE_3") (pintype "bidirectional"))
      (node (ref "Q9") (pin "1") (pinfunction "SOURCE_1") (pintype "bidirectional"))
      (node (ref "Q9") (pin "2") (pinfunction "SOURCE_2") (pintype "bidirectional"))
      (node (ref "Q9") (pin "3") (pinfunction "SOURCE_3") (pintype "bidirectional"))
      (node (ref "R25") (pin "2") (pinfunction "2_2") (pintype "passive"))
      (node (ref "U$12") (pin "P$6") (pinfunction "SNSE_P$6") (pintype "bidirectional"))
    )
    (net (code "78") (name "PWR") (class "Default")
      (node (ref "J1") (pin "D6") (pinfunction "*D6_D6") (pintype "bidirectional"))
      (node (ref "Q2") (pin "1") (pinfunction "G_1") (pintype "passive"))
      (node (ref "R10") (pin "2") (pinfunction "2_2") (pintype "passive"))
      (node (ref "U$6") (pin "27") (pinfunction "PD7(ADC10)_27") (pintype "bidirectional"))
    )
    (net (code "79") (name "RESET") (class "Default")
      (node (ref "JP1") (pin "5") (pinfunction "5_5") (pintype "passive"))
      (node (ref "R28") (pin "1") (pinfunction "1_1") (pintype "passive"))
      (node (ref "U$6") (pin "13") (pinfunction "~{RESET}_13") (pintype "bidirectional"))
    )
    (net (code "80") (name "SCK") (class "Default")
      (node (ref "J1") (pin "D13") (pinfunction "D13_D13") (pintype "bidirectional"))
      (node (ref "JP1") (pin "3") (pinfunction "3_3") (pintype "passive"))
      (node (ref "U$5") (pin "41") (pinfunction "SCKI_41") (pintype "bidirectional"))
      (node (ref "U$6") (pin "9") (pinfunction "PB1(SCK)_9") (pintype "bidirectional"))
    )
    (net (code "81") (name "SCL") (class "Default")
      (node (ref "J1") (pin "SCL") (pinfunction "SCL_SCL") (pintype "bidirectional"))
      (node (ref "R15") (pin "1") (pinfunction "1_1") (pintype "passive"))
      (node (ref "U$13") (pin "P$8") (pinfunction "P$8_P$8") (pintype "bidirectional"))
      (node (ref "U$6") (pin "18") (pinfunction "PD0(SCL)_18") (pintype "bidirectional"))
    )
    (net (code "82") (name "SDA") (class "Default")
      (node (ref "J1") (pin "SDA") (pinfunction "SDA_SDA") (pintype "bidirectional"))
      (node (ref "R14") (pin "1") (pinfunction "1_1") (pintype "passive"))
      (node (ref "U$13") (pin "P$7") (pinfunction "P$7_P$7") (pintype "bidirectional"))
      (node (ref "U$6") (pin "19") (pinfunction "PD1(SDA)_19") (pintype "bidirectional"))
    )
    (net (code "83") (name "SS") (class "Default")
      (node (ref "J1") (pin "D10") (pinfunction "*D10_D10") (pintype "bidirectional"))
      (node (ref "U$5") (pin "44") (pinfunction "CSBI_44") (pintype "bidirectional"))
      (node (ref "U$6") (pin "8") (pinfunction "PB0(SS)_8") (pintype "bidirectional"))
    )
    (net (code "84") (name "START{slash}E-STOP1") (class "Default")
      (node (ref "Q10") (pin "G") (pinfunction "G_G") (pintype "passive"))
      (node (ref "R26") (pin "1") (pinfunction "1_1") (pintype "passive"))
      (node (ref "U$13") (pin "P$4") (pinfunction "P$4_P$4") (pintype "bidirectional"))
    )
    (net (code "85") (name "UGND") (class "Default")
      (node (ref "C15") (pin "1") (pinfunction "1_1") (pintype "passive"))
      (node (ref "L1") (pin "2") (pinfunction "2_2") (pintype "passive"))
      (node (ref "R31") (pin "1") (pinfunction "1_1") (pintype "passive"))
      (node (ref "U$6") (pin "5") (pinfunction "UGND_5") (pintype "bidirectional"))
      (node (ref "X1") (pin "5") (pinfunction "5_5") (pintype "passive"))
    )
    (net (code "86") (name "VREG") (class "Default")
      (node (ref "A0") (pin "1") (pinfunction "1_1") (pintype "passive"))
      (node (ref "A1") (pin "1") (pinfunction "1_1") (pintype "passive"))
      (node (ref "A2") (pin "1") (pinfunction "1_1") (pintype "passive"))
      (node (ref "A3") (pin "1") (pinfunction "1_1") (pintype "passive"))
      (node (ref "C4") (pin "1") (pinfunction "1_1") (pintype "passive"))
      (node (ref "R11") (pin "2") (pinfunction "2_2") (pintype "passive"))
      (node (ref "TOS") (pin "1") (pinfunction "1_1") (pintype "passive"))
      (node (ref "U$5") (pin "31") (pinfunction "VREG_31") (pintype "bidirectional"))
    )
    (net (code "87") (name "VTEMP1") (class "Default")
      (node (ref "C7") (pin "2") (pinfunction "2_2") (pintype "passive"))
      (node (ref "R11") (pin "1") (pinfunction "1_1") (pintype "passive"))
      (node (ref "U$13") (pin "P$6") (pinfunction "P$6_P$6") (pintype "bidirectional"))
      (node (ref "U$5") (pin "28") (pinfunction "VTEMP1_28") (pintype "bidirectional"))
    )
    (net (code "88") (name "unconnected-(J1-*D3-PadD3)") (class "Default")
      (node (ref "J1") (pin "D3") (pinfunction "*D3_D3") (pintype "bidirectional"))
    )
    (net (code "89") (name "unconnected-(J1-*D5-PadD5)") (class "Default")
      (node (ref "J1") (pin "D5") (pinfunction "*D5_D5") (pintype "bidirectional"))
    )
    (net (code "90") (name "unconnected-(J1-Pad3.3V)") (class "Default")
      (node (ref "J1") (pin "3.3V") (pinfunction "3.3V_3.3V") (pintype "bidirectional"))
    )
    (net (code "91") (name "unconnected-(J1-PadA0)") (class "Default")
      (node (ref "J1") (pin "A0") (pinfunction "A0_A0") (pintype "bidirectional"))
    )
    (net (code "92") (name "unconnected-(J1-PadA1)") (class "Default")
      (node (ref "J1") (pin "A1") (pinfunction "A1_A1") (pintype "bidirectional"))
    )
    (net (code "93") (name "unconnected-(J1-PadA2)") (class "Default")
      (node (ref "J1") (pin "A2") (pinfunction "A2_A2") (pintype "bidirectional"))
    )
    (net (code "94") (name "unconnected-(J1-PadA3)") (class "Default")
      (node (ref "J1") (pin "A3") (pinfunction "A3_A3") (pintype "bidirectional"))
    )
    (net (code "95") (name "unconnected-(J1-PadA4)") (class "Default")
      (node (ref "J1") (pin "A4") (pinfunction "A4_A4") (pintype "bidirectional"))
    )
    (net (code "96") (name "unconnected-(J1-PadA5)") (class "Default")
      (node (ref "J1") (pin "A5") (pinfunction "A5_A5") (pintype "bidirectional"))
    )
    (net (code "97") (name "unconnected-(J1-PadAREF)") (class "Default")
      (node (ref "J1") (pin "AREF") (pinfunction "AREF_AREF") (pintype "bidirectional"))
    )
    (net (code "98") (name "unconnected-(J1-PadD2)") (class "Default")
      (node (ref "J1") (pin "D2") (pinfunction "D2_D2") (pintype "bidirectional"))
    )
    (net (code "99") (name "unconnected-(J1-PadD4)") (class "Default")
      (node (ref "J1") (pin "D4") (pinfunction "D4_D4") (pintype "bidirectional"))
    )
    (net (code "100") (name "unconnected-(J1-PadIOREF)") (class "Default")
      (node (ref "J1") (pin "IOREF") (pinfunction "IOREF_IOREF") (pintype "bidirectional"))
    )
    (net (code "101") (name "unconnected-(J1-PadRES)") (class "Default")
      (node (ref "J1") (pin "RES") (pinfunction "RES_RES") (pintype "bidirectional"))
    )
    (net (code "102") (name "unconnected-(J1-PadRX)") (class "Default")
      (node (ref "J1") (pin "RX") (pinfunction "RX_RX") (pintype "bidirectional"))
    )
    (net (code "103") (name "unconnected-(J1-PadTX)") (class "Default")
      (node (ref "J1") (pin "TX") (pinfunction "TX_TX") (pintype "bidirectional"))
    )
    (net (code "104") (name "unconnected-(J1-PadVIN)") (class "Default")
      (node (ref "J1") (pin "VIN") (pinfunction "VIN_VIN") (pintype "bidirectional"))
    )
    (net (code "105") (name "unconnected-(U$5-NC-Pad27)") (class "Default")
      (node (ref "U$5") (pin "27") (pinfunction "NC_27") (pintype "bidirectional"))
    )
    (net (code "106") (name "unconnected-(U$5-NC1-Pad33)") (class "Default")
      (node (ref "U$5") (pin "33") (pinfunction "NC1_33") (pintype "bidirectional"))
    )
    (net (code "107") (name "unconnected-(U$5-S7-Pad13)") (class "Default")
      (node (ref "U$5") (pin "13") (pinfunction "S7_13") (pintype "bidirectional"))
    )
    (net (code "108") (name "unconnected-(U$5-S8-Pad11)") (class "Default")
      (node (ref "U$5") (pin "11") (pinfunction "S8_11") (pintype "bidirectional"))
    )
    (net (code "109") (name "unconnected-(U$5-S9-Pad9)") (class "Default")
      (node (ref "U$5") (pin "9") (pinfunction "S9_9") (pintype "bidirectional"))
    )
    (net (code "110") (name "unconnected-(U$5-S10-Pad7)") (class "Default")
      (node (ref "U$5") (pin "7") (pinfunction "S10_7") (pintype "bidirectional"))
    )
    (net (code "111") (name "unconnected-(U$5-S11-Pad5)") (class "Default")
      (node (ref "U$5") (pin "5") (pinfunction "S11_5") (pintype "bidirectional"))
    )
    (net (code "112") (name "unconnected-(U$5-S12-Pad3)") (class "Default")
      (node (ref "U$5") (pin "3") (pinfunction "S12_3") (pintype "bidirectional"))
    )
    (net (code "113") (name "unconnected-(U$5-VTEMP2-Pad29)") (class "Default")
      (node (ref "U$5") (pin "29") (pinfunction "VTEMP2_29") (pintype "bidirectional"))
    )
    (net (code "114") (name "unconnected-(U$6-PB6(ADC13)-Pad30)") (class "Default")
      (node (ref "U$6") (pin "30") (pinfunction "PB6(ADC13)_30") (pintype "bidirectional"))
    )
    (net (code "115") (name "unconnected-(U$6-PB7-Pad12)") (class "Default")
      (node (ref "U$6") (pin "12") (pinfunction "PB7_12") (pintype "bidirectional"))
    )
    (net (code "116") (name "unconnected-(U$6-PC6-Pad31)") (class "Default")
      (node (ref "U$6") (pin "31") (pinfunction "PC6_31") (pintype "bidirectional"))
    )
    (net (code "117") (name "unconnected-(U$6-PD2(RX)-Pad20)") (class "Default")
      (node (ref "U$6") (pin "20") (pinfunction "PD2(RX)_20") (pintype "bidirectional"))
    )
    (net (code "118") (name "unconnected-(U$6-PD3(TX)-Pad21)") (class "Default")
      (node (ref "U$6") (pin "21") (pinfunction "PD3(TX)_21") (pintype "bidirectional"))
    )
    (net (code "119") (name "unconnected-(U$6-PD4(ADC8)-Pad25)") (class "Default")
      (node (ref "U$6") (pin "25") (pinfunction "PD4(ADC8)_25") (pintype "bidirectional"))
    )
    (net (code "120") (name "unconnected-(U$6-PD5-Pad22)") (class "Default")
      (node (ref "U$6") (pin "22") (pinfunction "PD5_22") (pintype "bidirectional"))
    )
    (net (code "121") (name "unconnected-(U$6-PD6(ADC9)-Pad26)") (class "Default")
      (node (ref "U$6") (pin "26") (pinfunction "PD6(ADC9)_26") (pintype "bidirectional"))
    )
    (net (code "122") (name "unconnected-(U$6-PF0(ADC0)-Pad41)") (class "Default")
      (node (ref "U$6") (pin "41") (pinfunction "PF0(ADC0)_41") (pintype "bidirectional"))
    )
    (net (code "123") (name "unconnected-(U$6-PF1(ADC1)-Pad40)") (class "Default")
      (node (ref "U$6") (pin "40") (pinfunction "PF1(ADC1)_40") (pintype "bidirectional"))
    )
    (net (code "124") (name "unconnected-(U$6-PF4(ADC4)-Pad39)") (class "Default")
      (node (ref "U$6") (pin "39") (pinfunction "PF4(ADC4)_39") (pintype "bidirectional"))
    )
    (net (code "125") (name "unconnected-(U$6-PF5(ADC5)-Pad38)") (class "Default")
      (node (ref "U$6") (pin "38") (pinfunction "PF5(ADC5)_38") (pintype "bidirectional"))
    )
    (net (code "126") (name "unconnected-(U$6-PF6(ADC6)-Pad37)") (class "Default")
      (node (ref "U$6") (pin "37") (pinfunction "PF6(ADC6)_37") (pintype "bidirectional"))
    )
    (net (code "127") (name "unconnected-(U$6-PF7(ADC7)-Pad36)") (class "Default")
      (node (ref "U$6") (pin "36") (pinfunction "PF7(ADC7)_36") (pintype "bidirectional"))
    )
    (net (code "128") (name "unconnected-(X1-Pad4)") (class "Default")
      (node (ref "X1") (pin "4") (pinfunction "4_4") (pintype "passive"))
    )
  )
)
